# motor_board.net
KiCad netlist of a schematic drawn in EAGLE
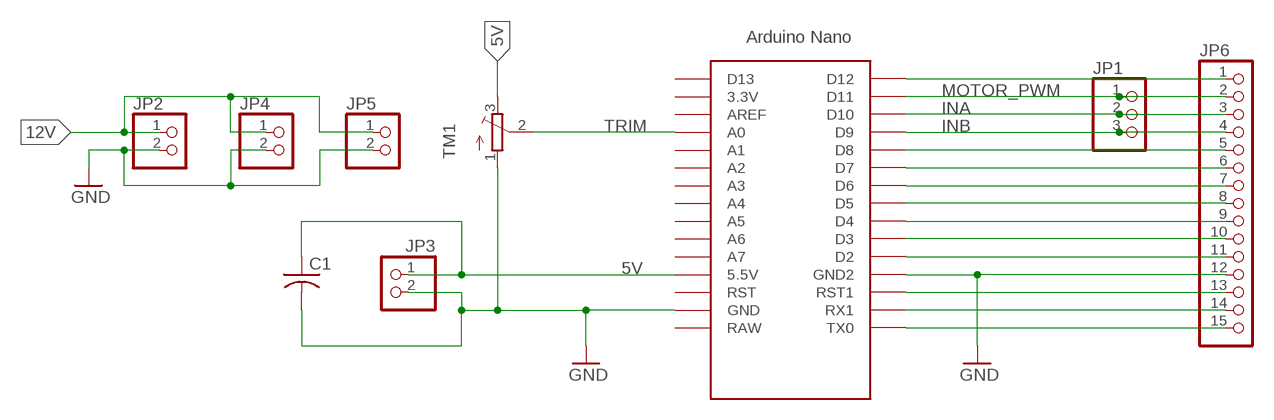
[diagram p0: schematic, sheet 1]

(export (version "E")
  (design (tool "Eeschema 10.0.6"))
  (components
    (comp (ref "C1")
      (value "C-US025-060X050")
      (footprint "eagle-import:C025-060X050")
      (libsource (lib "eagle-import") (part "C-US025-060X050"))
    )
    (comp (ref "JP1")
      (value "PINHD-1X3")
      (footprint "eagle-import:1X03")
      (libsource (lib "eagle-import") (part "PINHD-1X3"))
    )
    (comp (ref "JP2")
      (value "PINHD-1X2")
      (footprint "eagle-import:1X02")
      (libsource (lib "eagle-import") (part "PINHD-1X2"))
    )
    (comp (ref "JP3")
      (value "PINHD-1X2")
      (footprint "eagle-import:1X02")
      (libsource (lib "eagle-import") (part "PINHD-1X2"))
    )
    (comp (ref "JP4")
      (value "PINHD-1X2")
      (footprint "eagle-import:1X02")
      (libsource (lib "eagle-import") (part "PINHD-1X2"))
    )
    (comp (ref "JP5")
      (value "PINHD-1X2")
      (footprint "eagle-import:1X02")
      (libsource (lib "eagle-import") (part "PINHD-1X2"))
    )
    (comp (ref "JP6")
      (value "PINHD-1X15")
      (footprint "eagle-import:1X15")
      (libsource (lib "eagle-import") (part "PINHD-1X15"))
    )
    (comp (ref "TM1")
      (value "TRIMPOT3386")
      (footprint "eagle-import:TRIM-3386")
      (libsource (lib "eagle-import") (part "TRIMPOT3386"))
    )
    (comp (ref "U$2")
      (value "NANO")
      (footprint "eagle-import:NANO")
      (libsource (lib "eagle-import") (part "NANO"))
    )
  )
  (nets
    (net (code "1") (name "/INA") (class "Default")
      (node (ref "JP1") (pin "2") (pinfunction "2_2") (pintype "passive"))
      (node (ref "JP6") (pin "3") (pinfunction "3_3") (pintype "passive"))
      (node (ref "U$2") (pin "D10") (pinfunction "D10_D10") (pintype "bidirectional"))
    )
    (net (code "2") (name "/INB") (class "Default")
      (node (ref "JP1") (pin "3") (pinfunction "3_3") (pintype "passive"))
      (node (ref "JP6") (pin "4") (pinfunction "4_4") (pintype "passive"))
      (node (ref "U$2") (pin "D9") (pinfunction "D9_D9") (pintype "bidirectional"))
    )
    (net (code "3") (name "/MOTOR_PWM") (class "Default")
      (node (ref "JP1") (pin "1") (pinfunction "1_1") (pintype "passive"))
      (node (ref "JP6") (pin "2") (pinfunction "2_2") (pintype "passive"))
      (node (ref "U$2") (pin "D11") (pinfunction "D11_D11") (pintype "bidirectional"))
    )
    (net (code "4") (name "/TRIM") (class "Default")
      (node (ref "TM1") (pin "2") (pinfunction "S_2") (pintype "passive"))
      (node (ref "U$2") (pin "A0") (pinfunction "A0_A0") (pintype "bidirectional"))
    )
    (net (code "5") (name "5V") (class "Default")
      (node (ref "C1") (pin "1") (pinfunction "1_1") (pintype "passive"))
      (node (ref "JP3") (pin "1") (pinfunction "1_1") (pintype "passive"))
      (node (ref "TM1") (pin "3") (pinfunction "E_3") (pintype "passive"))
      (node (ref "U$2") (pin "5V") (pinfunction "5.5V_5V") (pintype "bidirectional"))
    )
    (net (code "6") (name "12V") (class "Default")
      (node (ref "JP2") (pin "1") (pinfunction "1_1") (pintype "passive"))
      (node (ref "JP4") (pin "1") (pinfunction "1_1") (pintype "passive"))
      (node (ref "JP5") (pin "1") (pinfunction "1_1") (pintype "passive"))
    )
    (net (code "7") (name "GND") (class "Default")
      (node (ref "C1") (pin "2") (pinfunction "2_2") (pintype "passive"))
      (node (ref "JP2") (pin "2") (pinfunction "2_2") (pintype "passive"))
      (node (ref "JP3") (pin "2") (pinfunction "2_2") (pintype "passive"))
      (node (ref "JP4") (pin "2") (pinfunction "2_2") (pintype "passive"))
      (node (ref "JP5") (pin "2") (pinfunction "2_2") (pintype "passive"))
      (node (ref "JP6") (pin "12") (pinfunction "12_12") (pintype "passive"))
      (node (ref "TM1") (pin "1") (pinfunction "A_1") (pintype "passive"))
      (node (ref "U$2") (pin "GND") (pinfunction "GND_GND") (pintype "bidirectional"))
      (node (ref "U$2") (pin "GND1") (pinfunction "GND2_GND1") (pintype "bidirectional"))
    )
    (net (code "8") (name "Net-(JP6-Pad1)") (class "Default")
      (node (ref "JP6") (pin "1") (pinfunction "1_1") (pintype "passive"))
      (node (ref "U$2") (pin "D12") (pinfunction "D12_D12") (pintype "bidirectional"))
    )
    (net (code "9") (name "Net-(JP6-Pad5)") (class "Default")
      (node (ref "JP6") (pin "5") (pinfunction "5_5") (pintype "passive"))
      (node (ref "U$2") (pin "D8") (pinfunction "D8_D8") (pintype "bidirectional"))
    )
    (net (code "10") (name "Net-(JP6-Pad6)") (class "Default")
      (node (ref "JP6") (pin "6") (pinfunction "6_6") (pintype "passive"))
      (node (ref "U$2") (pin "D7") (pinfunction "D7_D7") (pintype "bidirectional"))
    )
    (net (code "11") (name "Net-(JP6-Pad7)") (class "Default")
      (node (ref "JP6") (pin "7") (pinfunction "7_7") (pintype "passive"))
      (node (ref "U$2") (pin "D6") (pinfunction "D6_D6") (pintype "bidirectional"))
    )
    (net (code "12") (name "Net-(JP6-Pad8)") (class "Default")
      (node (ref "JP6") (pin "8") (pinfunction "8_8") (pintype "passive"))
      (node (ref "U$2") (pin "D5") (pinfunction "D5_D5") (pintype "bidirectional"))
    )
    (net (code "13") (name "Net-(JP6-Pad9)") (class "Default")
      (node (ref "JP6") (pin "9") (pinfunction "9_9") (pintype "passive"))
      (node (ref "U$2") (pin "D4") (pinfunction "D4_D4") (pintype "bidirectional"))
    )
    (net (code "14") (name "Net-(JP6-Pad10)") (class "Default")
      (node (ref "JP6") (pin "10") (pinfunction "10_10") (pintype "passive"))
      (node (ref "U$2") (pin "D3") (pinfunction "D3_D3") (pintype "bidirectional"))
    )
    (net (code "15") (name "Net-(JP6-Pad11)") (class "Default")
      (node (ref "JP6") (pin "11") (pinfunction "11_11") (pintype "passive"))
      (node (ref "U$2") (pin "D2") (pinfunction "D2_D2") (pintype "bidirectional"))
    )
    (net (code "16") (name "Net-(JP6-Pad13)") (class "Default")
      (node (ref "JP6") (pin "13") (pinfunction "13_13") (pintype "passive"))
      (node (ref "U$2") (pin "RST1") (pinfunction "RST1_RST1") (pintype "bidirectional"))
    )
    (net (code "17") (name "Net-(JP6-Pad14)") (class "Default")
      (node (ref "JP6") (pin "14") (pinfunction "14_14") (pintype "passive"))
      (node (ref "U$2") (pin "RX1") (pinfunction "RX1_RX1") (pintype "bidirectional"))
    )
    (net (code "18") (name "Net-(JP6-Pad15)") (class "Default")
      (node (ref "JP6") (pin "15") (pinfunction "15_15") (pintype "passive"))
      (node (ref "U$2") (pin "TX0") (pinfunction "TX0_TX0") (pintype "bidirectional"))
    )
    (net (code "19") (name "unconnected-(U$2-Pad3.3V)") (class "Default")
      (node (ref "U$2") (pin "3.3V") (pinfunction "3.3V_3.3V") (pintype "bidirectional"))
    )
    (net (code "20") (name "unconnected-(U$2-PadA1)") (class "Default")
      (node (ref "U$2") (pin "A1") (pinfunction "A1_A1") (pintype "bidirectional"))
    )
    (net (code "21") (name "unconnected-(U$2-PadA2)") (class "Default")
      (node (ref "U$2") (pin "A2") (pinfunction "A2_A2") (pintype "bidirectional"))
    )
    (net (code "22") (name "unconnected-(U$2-PadA3)") (class "Default")
      (node (ref "U$2") (pin "A3") (pinfunction "A3_A3") (pintype "bidirectional"))
    )
    (net (code "23") (name "unconnected-(U$2-PadA4)") (class "Default")
      (node (ref "U$2") (pin "A4") (pinfunction "A4_A4") (pintype "bidirectional"))
    )
    (net (code "24") (name "unconnected-(U$2-PadA5)") (class "Default")
      (node (ref "U$2") (pin "A5") (pinfunction "A5_A5") (pintype "bidirectional"))
    )
    (net (code "25") (name "unconnected-(U$2-PadA6)") (class "Default")
      (node (ref "U$2") (pin "A6") (pinfunction "A6_A6") (pintype "bidirectional"))
    )
    (net (code "26") (name "unconnected-(U$2-PadA7)") (class "Default")
      (node (ref "U$2") (pin "A7") (pinfunction "A7_A7") (pintype "bidirectional"))
    )
    (net (code "27") (name "unconnected-(U$2-PadAREF)") (class "Default")
      (node (ref "U$2") (pin "AREF") (pinfunction "AREF_AREF") (pintype "bidirectional"))
    )
    (net (code "28") (name "unconnected-(U$2-PadD13)") (class "Default")
      (node (ref "U$2") (pin "D13") (pinfunction "D13_D13") (pintype "bidirectional"))
    )
    (net (code "29") (name "unconnected-(U$2-PadICSP1)") (class "Default")
      (node (ref "U$2") (pin "ICSP1") (pinfunction "ICSP1_ICSP1") (pintype "bidirectional"))
    )
    (net (code "30") (name "unconnected-(U$2-PadICSP2)") (class "Default")
      (node (ref "U$2") (pin "ICSP2") (pinfunction "ICSP2_ICSP2") (pintype "bidirectional"))
    )
    (net (code "31") (name "unconnected-(U$2-PadICSP3)") (class "Default")
      (node (ref "U$2") (pin "ICSP3") (pinfunction "ICSP3_ICSP3") (pintype "bidirectional"))
    )
    (net (code "32") (name "unconnected-(U$2-PadICSP4)") (class "Default")
      (node (ref "U$2") (pin "ICSP4") (pinfunction "ICSP4_ICSP4") (pintype "bidirectional"))
    )
    (net (code "33") (name "unconnected-(U$2-PadICSP5)") (class "Default")
      (node (ref "U$2") (pin "ICSP5") (pinfunction "ICSP5_ICSP5") (pintype "bidirectional"))
    )
    (net (code "34") (name "unconnected-(U$2-PadICSP6)") (class "Default")
      (node (ref "U$2") (pin "ICSP6") (pinfunction "ICSP6_ICSP6") (pintype "bidirectional"))
    )
    (net (code "35") (name "unconnected-(U$2-PadRAW)") (class "Default")
      (node (ref "U$2") (pin "RAW") (pinfunction "RAW_RAW") (pintype "bidirectional"))
    )
    (net (code "36") (name "unconnected-(U$2-PadRST)") (class "Default")
      (node (ref "U$2") (pin "RST") (pinfunction "RST_RST") (pintype "bidirectional"))
    )
  )
)
